# LED.net
KiCad netlist of a schematic drawn in Altium Designer
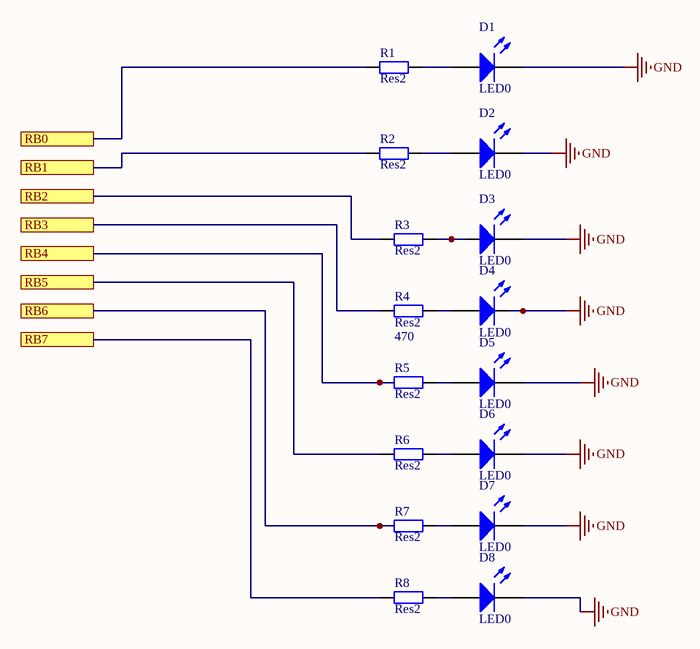
[diagram p0: LED.SchDoc]

(export (version "E")
  (design (tool "Eeschema 10.0.6"))
  (components
    (comp (ref "D1")
      (value "LED0")
      (footprint "LED-0")
      (description "Typical INFRARED GaAs LED")
      (fields (field (name "PUBLISHER") "Altium Limited"))
      (libsource (lib "Miscellaneous Devices") (part "LED0"))
    )
    (comp (ref "D2")
      (value "LED0")
      (footprint "LED-0")
      (description "Typical INFRARED GaAs LED")
      (fields (field (name "PUBLISHER") "Altium Limited"))
      (libsource (lib "Miscellaneous Devices") (part "LED0"))
    )
    (comp (ref "D3")
      (value "LED0")
      (footprint "LED-0")
      (description "Typical INFRARED GaAs LED")
      (fields (field (name "PUBLISHER") "Altium Limited"))
      (libsource (lib "Miscellaneous Devices") (part "LED0"))
    )
    (comp (ref "D4")
      (value "LED0")
      (footprint "LED-0")
      (description "Typical INFRARED GaAs LED")
      (fields (field (name "PUBLISHER") "Altium Limited"))
      (libsource (lib "Miscellaneous Devices") (part "LED0"))
    )
    (comp (ref "D5")
      (value "LED0")
      (footprint "LED-0")
      (description "Typical INFRARED GaAs LED")
      (fields (field (name "PUBLISHER") "Altium Limited"))
      (libsource (lib "Miscellaneous Devices") (part "LED0"))
    )
    (comp (ref "D6")
      (value "LED0")
      (footprint "LED-0")
      (description "Typical INFRARED GaAs LED")
      (fields (field (name "PUBLISHER") "Altium Limited"))
      (libsource (lib "Miscellaneous Devices") (part "LED0"))
    )
    (comp (ref "D7")
      (value "LED0")
      (footprint "LED-0")
      (description "Typical INFRARED GaAs LED")
      (fields (field (name "PUBLISHER") "Altium Limited"))
      (libsource (lib "Miscellaneous Devices") (part "LED0"))
    )
    (comp (ref "D8")
      (value "LED0")
      (footprint "LED-0")
      (description "Typical INFRARED GaAs LED")
      (fields (field (name "PUBLISHER") "Altium Limited"))
      (libsource (lib "Miscellaneous Devices") (part "LED0"))
    )
    (comp (ref "R1")
      (value "Res2")
      (footprint "AXIAL-0.4")
      (description "Resistor")
      (fields (field (name "PUBLISHER") "Altium Limited"))
      (libsource (lib "Miscellaneous Devices") (part "Res2"))
    )
    (comp (ref "R2")
      (value "Res2")
      (footprint "AXIAL-0.4")
      (description "Resistor")
      (fields (field (name "PUBLISHER") "Altium Limited"))
      (libsource (lib "Miscellaneous Devices") (part "Res2"))
    )
    (comp (ref "R3")
      (value "Res2")
      (footprint "AXIAL-0.4")
      (description "Resistor")
      (fields (field (name "PUBLISHER") "Altium Limited"))
      (libsource (lib "Miscellaneous Devices") (part "Res2"))
    )
    (comp (ref "R4")
      (value "Res2")
      (footprint "AXIAL-0.4")
      (description "Resistor")
      (fields (field (name "ALTIUM_VALUE") "470") (field (name "PUBLISHER") "Altium Limited"))
      (libsource (lib "Miscellaneous Devices") (part "Res2"))
    )
    (comp (ref "R5")
      (value "Res2")
      (footprint "AXIAL-0.4")
      (description "Resistor")
      (fields (field (name "PUBLISHER") "Altium Limited"))
      (libsource (lib "Miscellaneous Devices") (part "Res2"))
    )
    (comp (ref "R6")
      (value "Res2")
      (footprint "AXIAL-0.4")
      (description "Resistor")
      (fields (field (name "PUBLISHER") "Altium Limited"))
      (libsource (lib "Miscellaneous Devices") (part "Res2"))
    )
    (comp (ref "R7")
      (value "Res2")
      (footprint "AXIAL-0.4")
      (description "Resistor")
      (fields (field (name "PUBLISHER") "Altium Limited"))
      (libsource (lib "Miscellaneous Devices") (part "Res2"))
    )
    (comp (ref "R8")
      (value "Res2")
      (footprint "AXIAL-0.4")
      (description "Resistor")
      (fields (field (name "PUBLISHER") "Altium Limited"))
      (libsource (lib "Miscellaneous Devices") (part "Res2"))
    )
  )
  (nets
    (net (code "1") (name "/RB0") (class "Default")
      (node (ref "R1") (pin "1") (pinfunction "1_1") (pintype "passive"))
    )
    (net (code "2") (name "/RB1") (class "Default")
      (node (ref "R2") (pin "1") (pinfunction "1_1") (pintype "passive"))
    )
    (net (code "3") (name "/RB2") (class "Default")
      (node (ref "R3") (pin "1") (pinfunction "1_1") (pintype "passive"))
    )
    (net (code "4") (name "/RB3") (class "Default")
      (node (ref "R4") (pin "1") (pinfunction "1_1") (pintype "passive"))
    )
    (net (code "5") (name "/RB4") (class "Default")
      (node (ref "R5") (pin "1") (pinfunction "1_1") (pintype "passive"))
    )
    (net (code "6") (name "/RB5") (class "Default")
      (node (ref "R6") (pin "1") (pinfunction "1_1") (pintype "passive"))
    )
    (net (code "7") (name "/RB6") (class "Default")
      (node (ref "R7") (pin "1") (pinfunction "1_1") (pintype "passive"))
    )
    (net (code "8") (name "/RB7") (class "Default")
      (node (ref "R8") (pin "1") (pinfunction "1_1") (pintype "passive"))
    )
    (net (code "9") (name "GND") (class "Default")
      (node (ref "D1") (pin "2") (pinfunction "K_2") (pintype "passive"))
      (node (ref "D2") (pin "2") (pinfunction "K_2") (pintype "passive"))
      (node (ref "D3") (pin "2") (pinfunction "K_2") (pintype "passive"))
      (node (ref "D4") (pin "2") (pinfunction "K_2") (pintype "passive"))
      (node (ref "D5") (pin "2") (pinfunction "K_2") (pintype "passive"))
      (node (ref "D6") (pin "2") (pinfunction "K_2") (pintype "passive"))
      (node (ref "D7") (pin "2") (pinfunction "K_2") (pintype "passive"))
      (node (ref "D8") (pin "2") (pinfunction "K_2") (pintype "passive"))
    )
    (net (code "10") (name "Net-(D1-A)") (class "Default")
      (node (ref "D1") (pin "1") (pinfunction "A_1") (pintype "passive"))
      (node (ref "R1") (pin "2") (pinfunction "2_2") (pintype "passive"))
    )
    (net (code "11") (name "Net-(D2-A)") (class "Default")
      (node (ref "D2") (pin "1") (pinfunction "A_1") (pintype "passive"))
      (node (ref "R2") (pin "2") (pinfunction "2_2") (pintype "passive"))
    )
    (net (code "12") (name "Net-(D3-A)") (class "Default")
      (node (ref "D3") (pin "1") (pinfunction "A_1") (pintype "passive"))
      (node (ref "R3") (pin "2") (pinfunction "2_2") (pintype "passive"))
    )
    (net (code "13") (name "Net-(D4-A)") (class "Default")
      (node (ref "D4") (pin "1") (pinfunction "A_1") (pintype "passive"))
      (node (ref "R4") (pin "2") (pinfunction "2_2") (pintype "passive"))
    )
    (net (code "14") (name "Net-(D5-A)") (class "Default")
      (node (ref "D5") (pin "1") (pinfunction "A_1") (pintype "passive"))
      (node (ref "R5") (pin "2") (pinfunction "2_2") (pintype "passive"))
    )
    (net (code "15") (name "Net-(D6-A)") (class "Default")
      (node (ref "D6") (pin "1") (pinfunction "A_1") (pintype "passive"))
      (node (ref "R6") (pin "2") (pinfunction "2_2") (pintype "passive"))
    )
    (net (code "16") (name "Net-(D7-A)") (class "Default")
      (node (ref "D7") (pin "1") (pinfunction "A_1") (pintype "passive"))
      (node (ref "R7") (pin "2") (pinfunction "2_2") (pintype "passive"))
    )
    (net (code "17") (name "Net-(D8-A)") (class "Default")
      (node (ref "D8") (pin "1") (pinfunction "A_1") (pintype "passive"))
      (node (ref "R8") (pin "2") (pinfunction "2_2") (pintype "passive"))
    )
  )
)
